# M2k_HC4052_multiplexer_board.net
KiCad netlist of a schematic drawn in EAGLE
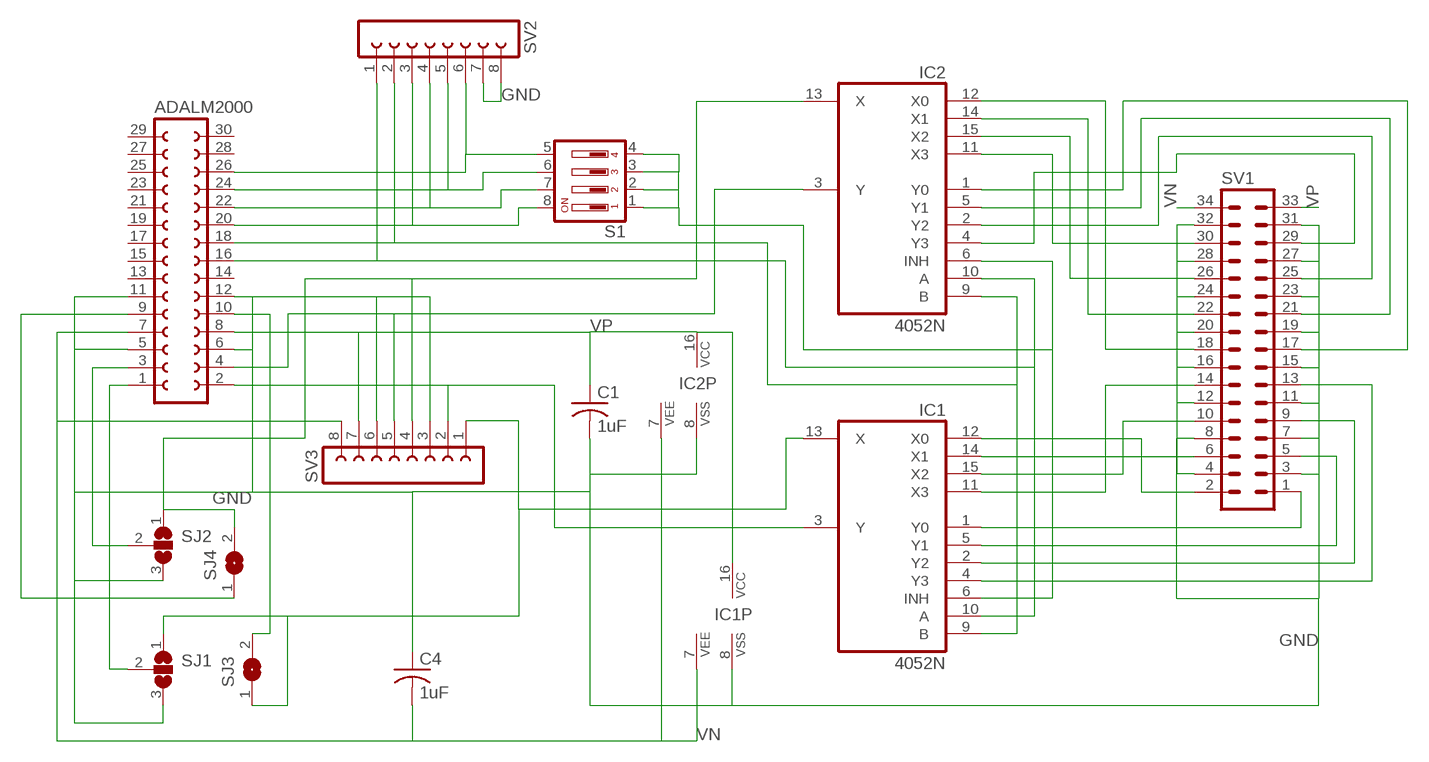
[diagram p0: schematic, sheet 1]

(export (version "E")
  (design (tool "Eeschema 10.0.6"))
  (components
    (comp (ref "ADALM2000")
      (value "FE15-2")
      (footprint "eagle-import:FE15-2")
      (libsource (lib "eagle-import") (part "FE15-2"))
    )
    (comp (ref "C1")
      (value "1uF")
      (footprint "eagle-import:C050-024X044")
      (libsource (lib "eagle-import") (part "C-US050-024X044"))
    )
    (comp (ref "C4")
      (value "1uF")
      (footprint "eagle-import:C050-024X044")
      (libsource (lib "eagle-import") (part "C-US050-024X044"))
    )
    (comp (ref "IC1")
      (value "4052N")
      (footprint "eagle-import:DIL16")
      (libsource (lib "eagle-import") (part "4052N"))
    )
    (comp (ref "IC2")
      (value "4052N")
      (footprint "eagle-import:DIL16")
      (libsource (lib "eagle-import") (part "4052N"))
    )
    (comp (ref "S1")
      (value "DIP04YL")
      (footprint "eagle-import:DIP04YL")
      (libsource (lib "eagle-import") (part "DIP04YL"))
    )
    (comp (ref "SJ1")
      (value "SJ2W")
      (footprint "eagle-import:SJ_2")
      (libsource (lib "eagle-import") (part "SJ2W"))
    )
    (comp (ref "SJ2")
      (value "SJ2W")
      (footprint "eagle-import:SJ_2")
      (libsource (lib "eagle-import") (part "SJ2W"))
    )
    (comp (ref "SJ3") (value "SJ") (footprint "eagle-import:SJ") (libsource (lib "eagle-import") (part "SJ")))
    (comp (ref "SJ4") (value "SJ") (footprint "eagle-import:SJ") (libsource (lib "eagle-import") (part "SJ")))
    (comp (ref "SV1")
      (value "MA17-2")
      (footprint "eagle-import:MA17-2")
      (libsource (lib "eagle-import") (part "MA17-2"))
    )
    (comp (ref "SV2")
      (value "FE08-1")
      (footprint "eagle-import:FE08")
      (libsource (lib "eagle-import") (part "FE08-1"))
    )
    (comp (ref "SV3")
      (value "FE08-1")
      (footprint "eagle-import:FE08")
      (libsource (lib "eagle-import") (part "FE08-1"))
    )
  )
  (nets
    (net (code "1") (name "/GND") (class "Default")
      (node (ref "ADALM2000") (pin "11") (pinfunction "11_11") (pintype "passive"))
      (node (ref "ADALM2000") (pin "12") (pinfunction "12_12") (pintype "passive"))
      (node (ref "ADALM2000") (pin "5") (pinfunction "5_5") (pintype "passive"))
      (node (ref "ADALM2000") (pin "6") (pinfunction "6_6") (pintype "passive"))
      (node (ref "C1") (pin "2") (pinfunction "2_2") (pintype "passive"))
      (node (ref "C4") (pin "1") (pinfunction "1_1") (pintype "passive"))
      (node (ref "IC1") (pin "8") (pinfunction "VSS_8") (pintype "power_in"))
      (node (ref "IC2") (pin "8") (pinfunction "VSS_8") (pintype "power_in"))
      (node (ref "SJ1") (pin "3") (pinfunction "3_3") (pintype "passive"))
      (node (ref "SJ2") (pin "3") (pinfunction "3_3") (pintype "passive"))
      (node (ref "SV1") (pin "11") (pinfunction "11_11") (pintype "passive"))
      (node (ref "SV1") (pin "12") (pinfunction "12_12") (pintype "passive"))
      (node (ref "SV1") (pin "15") (pinfunction "15_15") (pintype "passive"))
      (node (ref "SV1") (pin "16") (pinfunction "16_16") (pintype "passive"))
      (node (ref "SV1") (pin "19") (pinfunction "19_19") (pintype "passive"))
      (node (ref "SV1") (pin "20") (pinfunction "20_20") (pintype "passive"))
      (node (ref "SV1") (pin "23") (pinfunction "23_23") (pintype "passive"))
      (node (ref "SV1") (pin "24") (pinfunction "24_24") (pintype "passive"))
      (node (ref "SV1") (pin "27") (pinfunction "27_27") (pintype "passive"))
      (node (ref "SV1") (pin "28") (pinfunction "28_28") (pintype "passive"))
      (node (ref "SV1") (pin "3") (pinfunction "3_3") (pintype "passive"))
      (node (ref "SV1") (pin "31") (pinfunction "31_31") (pintype "passive"))
      (node (ref "SV1") (pin "32") (pinfunction "32_32") (pintype "passive"))
      (node (ref "SV1") (pin "4") (pinfunction "4_4") (pintype "passive"))
      (node (ref "SV1") (pin "7") (pinfunction "7_7") (pintype "passive"))
      (node (ref "SV1") (pin "8") (pinfunction "8_8") (pintype "passive"))
      (node (ref "SV2") (pin "7") (pinfunction "7_7") (pintype "passive"))
      (node (ref "SV2") (pin "8") (pinfunction "8_8") (pintype "passive"))
      (node (ref "SV3") (pin "3") (pinfunction "3_3") (pintype "passive"))
      (node (ref "SV3") (pin "6") (pinfunction "6_6") (pintype "passive"))
    )
    (net (code "2") (name "/VN") (class "Default")
      (node (ref "ADALM2000") (pin "7") (pinfunction "7_7") (pintype "passive"))
      (node (ref "C4") (pin "2") (pinfunction "2_2") (pintype "passive"))
      (node (ref "IC1") (pin "7") (pinfunction "VEE_7") (pintype "power_in"))
      (node (ref "IC2") (pin "7") (pinfunction "VEE_7") (pintype "power_in"))
      (node (ref "SV1") (pin "34") (pinfunction "34_34") (pintype "passive"))
      (node (ref "SV3") (pin "8") (pinfunction "8_8") (pintype "passive"))
    )
    (net (code "3") (name "/VP") (class "Default")
      (node (ref "ADALM2000") (pin "8") (pinfunction "8_8") (pintype "passive"))
      (node (ref "C1") (pin "1") (pinfunction "1_1") (pintype "passive"))
      (node (ref "IC1") (pin "16") (pinfunction "VCC_16") (pintype "power_in"))
      (node (ref "IC2") (pin "16") (pinfunction "VCC_16") (pintype "power_in"))
      (node (ref "SV1") (pin "33") (pinfunction "33_33") (pintype "passive"))
      (node (ref "SV3") (pin "7") (pinfunction "7_7") (pintype "passive"))
    )
    (net (code "4") (name "Net-(ADALM2000-Pad1)") (class "Default")
      (node (ref "ADALM2000") (pin "1") (pinfunction "1_1") (pintype "passive"))
      (node (ref "SJ1") (pin "2") (pinfunction "2_2") (pintype "passive"))
    )
    (net (code "5") (name "Net-(ADALM2000-Pad3)") (class "Default")
      (node (ref "ADALM2000") (pin "3") (pinfunction "3_3") (pintype "passive"))
      (node (ref "SJ2") (pin "2") (pinfunction "2_2") (pintype "passive"))
    )
    (net (code "6") (name "Net-(ADALM2000-Pad9)") (class "Default")
      (node (ref "ADALM2000") (pin "9") (pinfunction "9_9") (pintype "passive"))
      (node (ref "SJ4") (pin "1") (pinfunction "1_1") (pintype "passive"))
    )
    (net (code "7") (name "Net-(ADALM2000-Pad10)") (class "Default")
      (node (ref "ADALM2000") (pin "10") (pinfunction "10_10") (pintype "passive"))
      (node (ref "SJ3") (pin "2") (pinfunction "2_2") (pintype "passive"))
    )
    (net (code "8") (name "Net-(ADALM2000-Pad20)") (class "Default")
      (node (ref "ADALM2000") (pin "20") (pinfunction "20_20") (pintype "passive"))
      (node (ref "S1") (pin "8") (pinfunction "8_8") (pintype "passive"))
      (node (ref "SV2") (pin "3") (pinfunction "3_3") (pintype "passive"))
    )
    (net (code "9") (name "Net-(ADALM2000-Pad22)") (class "Default")
      (node (ref "ADALM2000") (pin "22") (pinfunction "22_22") (pintype "passive"))
      (node (ref "S1") (pin "7") (pinfunction "7_7") (pintype "passive"))
      (node (ref "SV2") (pin "4") (pinfunction "4_4") (pintype "passive"))
    )
    (net (code "10") (name "Net-(ADALM2000-Pad24)") (class "Default")
      (node (ref "ADALM2000") (pin "24") (pinfunction "24_24") (pintype "passive"))
      (node (ref "S1") (pin "6") (pinfunction "6_6") (pintype "passive"))
      (node (ref "SV2") (pin "5") (pinfunction "5_5") (pintype "passive"))
    )
    (net (code "11") (name "Net-(ADALM2000-Pad26)") (class "Default")
      (node (ref "ADALM2000") (pin "26") (pinfunction "26_26") (pintype "passive"))
      (node (ref "S1") (pin "5") (pinfunction "5_5") (pintype "passive"))
      (node (ref "SV2") (pin "6") (pinfunction "6_6") (pintype "passive"))
    )
    (net (code "12") (name "Net-(IC1A-A)") (class "Default")
      (node (ref "ADALM2000") (pin "16") (pinfunction "16_16") (pintype "passive"))
      (node (ref "IC1") (pin "10") (pinfunction "A_10") (pintype "input"))
      (node (ref "IC2") (pin "10") (pinfunction "A_10") (pintype "input"))
      (node (ref "SV2") (pin "1") (pinfunction "1_1") (pintype "passive"))
    )
    (net (code "13") (name "Net-(IC1A-B)") (class "Default")
      (node (ref "ADALM2000") (pin "18") (pinfunction "18_18") (pintype "passive"))
      (node (ref "IC1") (pin "9") (pinfunction "B_9") (pintype "input"))
      (node (ref "IC2") (pin "9") (pinfunction "B_9") (pintype "input"))
      (node (ref "SV2") (pin "2") (pinfunction "2_2") (pintype "passive"))
    )
    (net (code "14") (name "Net-(IC1A-INH)") (class "Default")
      (node (ref "IC1") (pin "6") (pinfunction "INH_6") (pintype "input"))
      (node (ref "IC2") (pin "6") (pinfunction "INH_6") (pintype "input"))
      (node (ref "S1") (pin "1") (pinfunction "1_1") (pintype "passive"))
      (node (ref "S1") (pin "2") (pinfunction "2_2") (pintype "passive"))
      (node (ref "S1") (pin "3") (pinfunction "3_3") (pintype "passive"))
      (node (ref "S1") (pin "4") (pinfunction "4_4") (pintype "passive"))
    )
    (net (code "15") (name "Net-(IC1A-X)") (class "Default")
      (node (ref "IC1") (pin "13") (pinfunction "X_13") (pintype "bidirectional"))
      (node (ref "SJ1") (pin "1") (pinfunction "1_1") (pintype "passive"))
      (node (ref "SJ3") (pin "1") (pinfunction "1_1") (pintype "passive"))
      (node (ref "SV3") (pin "1") (pinfunction "1_1") (pintype "passive"))
    )
    (net (code "16") (name "Net-(IC1A-X0)") (class "Default")
      (node (ref "IC1") (pin "12") (pinfunction "X0_12") (pintype "bidirectional"))
      (node (ref "SV1") (pin "2") (pinfunction "2_2") (pintype "passive"))
    )
    (net (code "17") (name "Net-(IC1A-X1)") (class "Default")
      (node (ref "IC1") (pin "14") (pinfunction "X1_14") (pintype "bidirectional"))
      (node (ref "SV1") (pin "6") (pinfunction "6_6") (pintype "passive"))
    )
    (net (code "18") (name "Net-(IC1A-X2)") (class "Default")
      (node (ref "IC1") (pin "15") (pinfunction "X2_15") (pintype "bidirectional"))
      (node (ref "SV1") (pin "10") (pinfunction "10_10") (pintype "passive"))
    )
    (net (code "19") (name "Net-(IC1A-X3)") (class "Default")
      (node (ref "IC1") (pin "11") (pinfunction "X3_11") (pintype "bidirectional"))
      (node (ref "SV1") (pin "14") (pinfunction "14_14") (pintype "passive"))
    )
    (net (code "20") (name "Net-(IC1A-Y)") (class "Default")
      (node (ref "ADALM2000") (pin "2") (pinfunction "2_2") (pintype "passive"))
      (node (ref "IC1") (pin "3") (pinfunction "Y_3") (pintype "bidirectional"))
      (node (ref "SV3") (pin "2") (pinfunction "2_2") (pintype "passive"))
    )
    (net (code "21") (name "Net-(IC1A-Y0)") (class "Default")
      (node (ref "IC1") (pin "1") (pinfunction "Y0_1") (pintype "bidirectional"))
      (node (ref "SV1") (pin "1") (pinfunction "1_1") (pintype "passive"))
    )
    (net (code "22") (name "Net-(IC1A-Y1)") (class "Default")
      (node (ref "IC1") (pin "5") (pinfunction "Y1_5") (pintype "bidirectional"))
      (node (ref "SV1") (pin "5") (pinfunction "5_5") (pintype "passive"))
    )
    (net (code "23") (name "Net-(IC1A-Y2)") (class "Default")
      (node (ref "IC1") (pin "2") (pinfunction "Y2_2") (pintype "bidirectional"))
      (node (ref "SV1") (pin "9") (pinfunction "9_9") (pintype "passive"))
    )
    (net (code "24") (name "Net-(IC1A-Y3)") (class "Default")
      (node (ref "IC1") (pin "4") (pinfunction "Y3_4") (pintype "bidirectional"))
      (node (ref "SV1") (pin "13") (pinfunction "13_13") (pintype "passive"))
    )
    (net (code "25") (name "Net-(IC2A-X)") (class "Default")
      (node (ref "IC2") (pin "13") (pinfunction "X_13") (pintype "bidirectional"))
      (node (ref "SJ2") (pin "1") (pinfunction "1_1") (pintype "passive"))
      (node (ref "SJ4") (pin "2") (pinfunction "2_2") (pintype "passive"))
      (node (ref "SV3") (pin "4") (pinfunction "4_4") (pintype "passive"))
    )
    (net (code "26") (name "Net-(IC2A-X0)") (class "Default")
      (node (ref "IC2") (pin "12") (pinfunction "X0_12") (pintype "bidirectional"))
      (node (ref "SV1") (pin "18") (pinfunction "18_18") (pintype "passive"))
    )
    (net (code "27") (name "Net-(IC2A-X1)") (class "Default")
      (node (ref "IC2") (pin "14") (pinfunction "X1_14") (pintype "bidirectional"))
      (node (ref "SV1") (pin "22") (pinfunction "22_22") (pintype "passive"))
    )
    (net (code "28") (name "Net-(IC2A-X2)") (class "Default")
      (node (ref "IC2") (pin "15") (pinfunction "X2_15") (pintype "bidirectional"))
      (node (ref "SV1") (pin "26") (pinfunction "26_26") (pintype "passive"))
    )
    (net (code "29") (name "Net-(IC2A-X3)") (class "Default")
      (node (ref "IC2") (pin "11") (pinfunction "X3_11") (pintype "bidirectional"))
      (node (ref "SV1") (pin "30") (pinfunction "30_30") (pintype "passive"))
    )
    (net (code "30") (name "Net-(IC2A-Y)") (class "Default")
      (node (ref "ADALM2000") (pin "4") (pinfunction "4_4") (pintype "passive"))
      (node (ref "IC2") (pin "3") (pinfunction "Y_3") (pintype "bidirectional"))
      (node (ref "SV3") (pin "5") (pinfunction "5_5") (pintype "passive"))
    )
    (net (code "31") (name "Net-(IC2A-Y0)") (class "Default")
      (node (ref "IC2") (pin "1") (pinfunction "Y0_1") (pintype "bidirectional"))
      (node (ref "SV1") (pin "17") (pinfunction "17_17") (pintype "passive"))
    )
    (net (code "32") (name "Net-(IC2A-Y1)") (class "Default")
      (node (ref "IC2") (pin "5") (pinfunction "Y1_5") (pintype "bidirectional"))
      (node (ref "SV1") (pin "21") (pinfunction "21_21") (pintype "passive"))
    )
    (net (code "33") (name "Net-(IC2A-Y2)") (class "Default")
      (node (ref "IC2") (pin "2") (pinfunction "Y2_2") (pintype "bidirectional"))
      (node (ref "SV1") (pin "25") (pinfunction "25_25") (pintype "passive"))
    )
    (net (code "34") (name "Net-(IC2A-Y3)") (class "Default")
      (node (ref "IC2") (pin "4") (pinfunction "Y3_4") (pintype "bidirectional"))
      (node (ref "SV1") (pin "29") (pinfunction "29_29") (pintype "passive"))
    )
    (net (code "35") (name "unconnected-(ADALM2000-Pad13)") (class "Default")
      (node (ref "ADALM2000") (pin "13") (pinfunction "13_13") (pintype "passive"))
    )
    (net (code "36") (name "unconnected-(ADALM2000-Pad14)") (class "Default")
      (node (ref "ADALM2000") (pin "14") (pinfunction "14_14") (pintype "passive"))
    )
    (net (code "37") (name "unconnected-(ADALM2000-Pad15)") (class "Default")
      (node (ref "ADALM2000") (pin "15") (pinfunction "15_15") (pintype "passive"))
    )
    (net (code "38") (name "unconnected-(ADALM2000-Pad17)") (class "Default")
      (node (ref "ADALM2000") (pin "17") (pinfunction "17_17") (pintype "passive"))
    )
    (net (code "39") (name "unconnected-(ADALM2000-Pad19)") (class "Default")
      (node (ref "ADALM2000") (pin "19") (pinfunction "19_19") (pintype "passive"))
    )
    (net (code "40") (name "unconnected-(ADALM2000-Pad21)") (class "Default")
      (node (ref "ADALM2000") (pin "21") (pinfunction "21_21") (pintype "passive"))
    )
    (net (code "41") (name "unconnected-(ADALM2000-Pad23)") (class "Default")
      (node (ref "ADALM2000") (pin "23") (pinfunction "23_23") (pintype "passive"))
    )
    (net (code "42") (name "unconnected-(ADALM2000-Pad25)") (class "Default")
      (node (ref "ADALM2000") (pin "25") (pinfunction "25_25") (pintype "passive"))
    )
    (net (code "43") (name "unconnected-(ADALM2000-Pad27)") (class "Default")
      (node (ref "ADALM2000") (pin "27") (pinfunction "27_27") (pintype "passive"))
    )
    (net (code "44") (name "unconnected-(ADALM2000-Pad28)") (class "Default")
      (node (ref "ADALM2000") (pin "28") (pinfunction "28_28") (pintype "passive"))
    )
    (net (code "45") (name "unconnected-(ADALM2000-Pad29)") (class "Default")
      (node (ref "ADALM2000") (pin "29") (pinfunction "29_29") (pintype "passive"))
    )
    (net (code "46") (name "unconnected-(ADALM2000-Pad30)") (class "Default")
      (node (ref "ADALM2000") (pin "30") (pinfunction "30_30") (pintype "passive"))
    )
  )
)
